# SIPM_readout.net
KiCad netlist of a schematic drawn in EAGLE
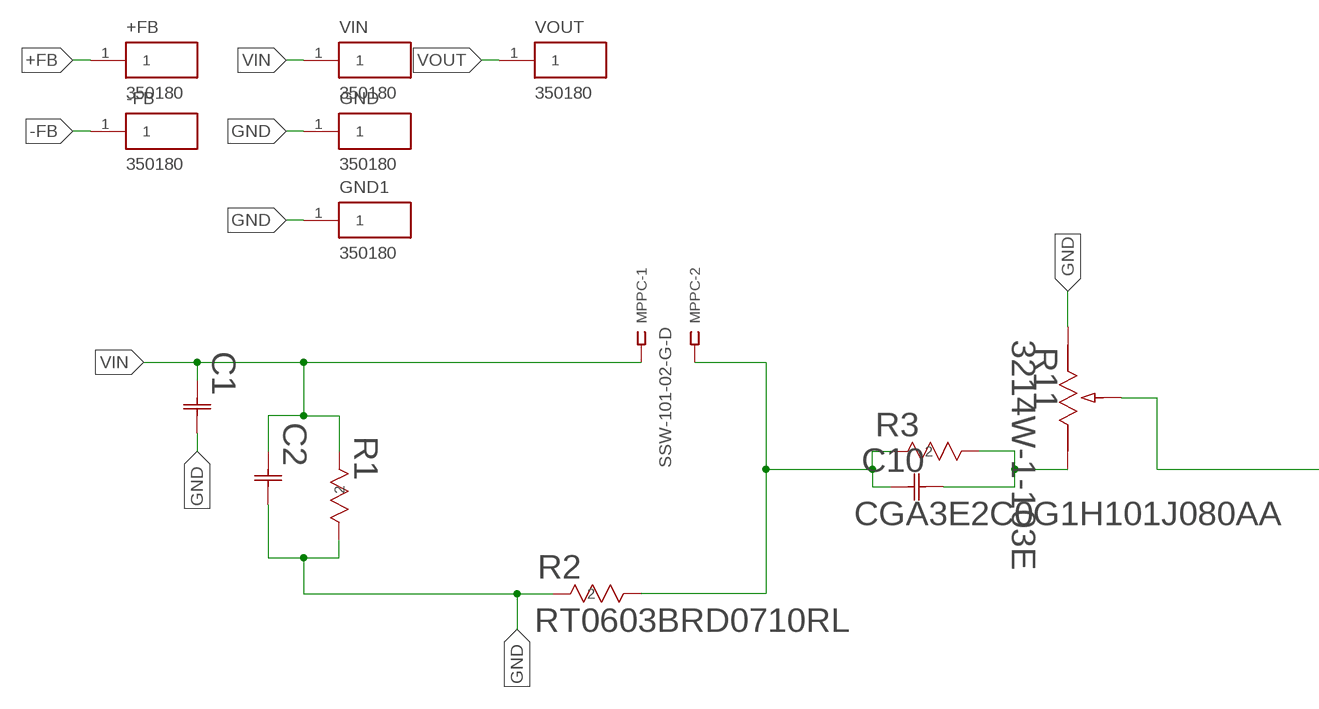
[diagram p0: schematic, sheet 1, part 1 of 2]
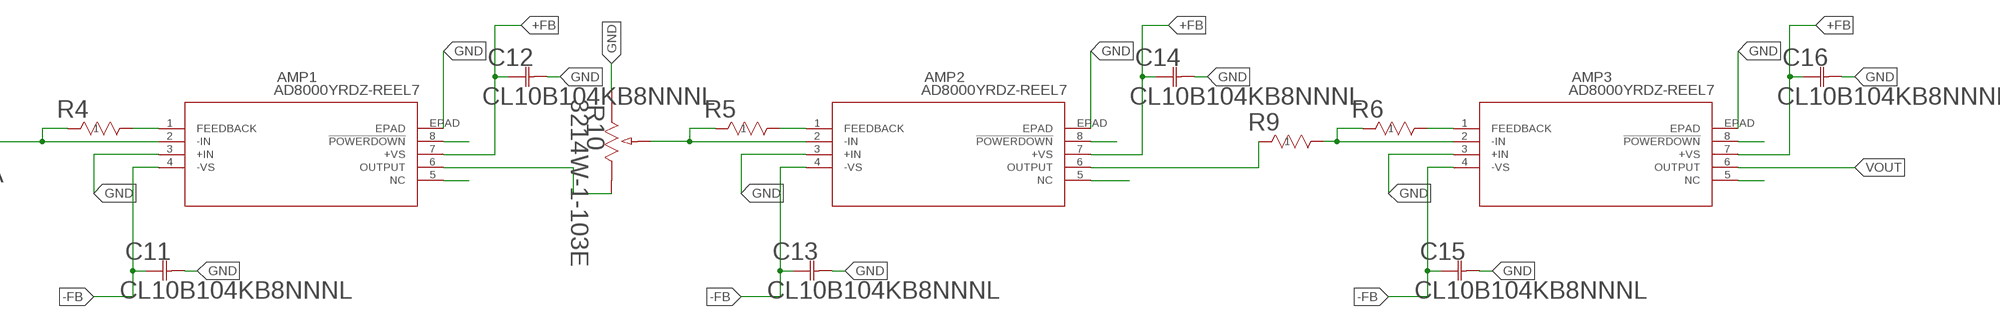
[diagram p1: schematic, sheet 1, part 2 of 2]

(export (version "E")
  (design (tool "Eeschema 10.0.6"))
  (components
    (comp (ref "+FB")
      (value "350180")
      (footprint "eagle-import:TE_350180")
      (fields (field (name "MF") "TE Connectivity"))
      (libsource (lib "eagle-import") (part "350180"))
    )
    (comp (ref "-FB")
      (value "350180")
      (footprint "eagle-import:TE_350180")
      (fields (field (name "MF") "TE Connectivity"))
      (libsource (lib "eagle-import") (part "350180"))
    )
    (comp (ref "AMP1")
      (value "AD8000YRDZ-REEL7")
      (footprint "eagle-import:RD_8_1_ADI")
      (fields (field (name "COPYRIGHT") "Copyright (C) 2018 Accelerated Designs. All rights reserved"))
      (libsource (lib "eagle-import") (part "AD8000YRDZ-REEL7"))
    )
    (comp (ref "AMP2")
      (value "AD8000YRDZ-REEL7")
      (footprint "eagle-import:RD_8_1_ADI")
      (fields (field (name "COPYRIGHT") "Copyright (C) 2018 Accelerated Designs. All rights reserved"))
      (libsource (lib "eagle-import") (part "AD8000YRDZ-REEL7"))
    )
    (comp (ref "AMP3")
      (value "AD8000YRDZ-REEL7")
      (footprint "eagle-import:RD_8_1_ADI")
      (fields (field (name "COPYRIGHT") "Copyright (C) 2018 Accelerated Designs. All rights reserved"))
      (libsource (lib "eagle-import") (part "AD8000YRDZ-REEL7"))
    )
    (comp (ref "C1")
      (value "CGA6P3X7R1H335K250AB")
      (footprint "eagle-import:CAP_3225_TDK")
      (libsource (lib "eagle-import") (part "CGA6P3X7R1H335K250AB"))
    )
    (comp (ref "C2")
      (value "C3225X7R1H105K160AA")
      (footprint "eagle-import:CAP_3225_TDK")
      (libsource (lib "eagle-import") (part "C3225X7R1H105K160AA"))
    )
    (comp (ref "C10")
      (value "CGA3E2C0G1H101J080AA")
      (footprint "eagle-import:CAP_1608_TDK")
      (libsource (lib "eagle-import") (part "CGA3E2C0G1H101J080AA"))
    )
    (comp (ref "C11")
      (value "CL10B104KB8NNNL")
      (footprint "eagle-import:CAP_CL10_SAM")
      (fields (field (name "COPYRIGHT") "Copyright (C) 2018 Accelerated Designs. All rights reserved"))
      (libsource (lib "eagle-import") (part "CL10B104KB8NNNL"))
    )
    (comp (ref "C12")
      (value "CL10B104KB8NNNL")
      (footprint "eagle-import:CAP_CL10_SAM")
      (fields (field (name "COPYRIGHT") "Copyright (C) 2018 Accelerated Designs. All rights reserved"))
      (libsource (lib "eagle-import") (part "CL10B104KB8NNNL"))
    )
    (comp (ref "C13")
      (value "CL10B104KB8NNNL")
      (footprint "eagle-import:CAP_CL10_SAM")
      (fields (field (name "COPYRIGHT") "Copyright (C) 2018 Accelerated Designs. All rights reserved"))
      (libsource (lib "eagle-import") (part "CL10B104KB8NNNL"))
    )
    (comp (ref "C14")
      (value "CL10B104KB8NNNL")
      (footprint "eagle-import:CAP_CL10_SAM")
      (fields (field (name "COPYRIGHT") "Copyright (C) 2018 Accelerated Designs. All rights reserved"))
      (libsource (lib "eagle-import") (part "CL10B104KB8NNNL"))
    )
    (comp (ref "C15")
      (value "CL10B104KB8NNNL")
      (footprint "eagle-import:CAP_CL10_SAM")
      (fields (field (name "COPYRIGHT") "Copyright (C) 2018 Accelerated Designs. All rights reserved"))
      (libsource (lib "eagle-import") (part "CL10B104KB8NNNL"))
    )
    (comp (ref "C16")
      (value "CL10B104KB8NNNL")
      (footprint "eagle-import:CAP_CL10_SAM")
      (fields (field (name "COPYRIGHT") "Copyright (C) 2018 Accelerated Designs. All rights reserved"))
      (libsource (lib "eagle-import") (part "CL10B104KB8NNNL"))
    )
    (comp (ref "GND")
      (value "350180")
      (footprint "eagle-import:TE_350180")
      (fields (field (name "MF") "TE Connectivity"))
      (libsource (lib "eagle-import") (part "350180"))
    )
    (comp (ref "GND1")
      (value "350180")
      (footprint "eagle-import:TE_350180")
      (fields (field (name "MF") "TE Connectivity"))
      (libsource (lib "eagle-import") (part "350180"))
    )
    (comp (ref "MPPC")
      (value "SSW-101-02-G-D")
      (footprint "eagle-import:SSW-101-02-G-D")
      (fields (field (name "MF") "Samtec Inc."))
      (libsource (lib "eagle-import") (part "SSW-101-02-G-D"))
    )
    (comp (ref "R1")
      (value "RC0603FR-072ML")
      (footprint "eagle-import:RC0603N_YAG")
      (libsource (lib "eagle-import") (part "RC0603FR-072ML"))
    )
    (comp (ref "R2")
      (value "RT0603BRD0710RL")
      (footprint "eagle-import:RC0603N_YAG")
      (libsource (lib "eagle-import") (part "RT0603BRD0710RL"))
    )
    (comp (ref "R3")
      (value "RT0603BRD0710RL")
      (footprint "eagle-import:RC0603N_YAG")
      (libsource (lib "eagle-import") (part "RT0603BRD0710RL"))
    )
    (comp (ref "R4")
      (value "ESR03EZPF1001")
      (footprint "eagle-import:RES_R0603_ROM")
      (libsource (lib "eagle-import") (part "ESR03EZPF1001"))
    )
    (comp (ref "R5")
      (value "ESR03EZPF1001")
      (footprint "eagle-import:RES_R0603_ROM")
      (libsource (lib "eagle-import") (part "ESR03EZPF1001"))
    )
    (comp (ref "R6")
      (value "ESR03EZPF1001")
      (footprint "eagle-import:RES_R0603_ROM")
      (libsource (lib "eagle-import") (part "ESR03EZPF1001"))
    )
    (comp (ref "R9")
      (value "ESR03EZPF1001")
      (footprint "eagle-import:RES_R0603_ROM")
      (libsource (lib "eagle-import") (part "ESR03EZPF1001"))
    )
    (comp (ref "R10")
      (value "3214W-1-103E")
      (footprint "eagle-import:POT_3214W")
      (libsource (lib "eagle-import") (part "3214W-1-103E"))
    )
    (comp (ref "R11")
      (value "3214W-1-103E")
      (footprint "eagle-import:POT_3214W")
      (libsource (lib "eagle-import") (part "3214W-1-103E"))
    )
    (comp (ref "VIN")
      (value "350180")
      (footprint "eagle-import:TE_350180")
      (fields (field (name "MF") "TE Connectivity"))
      (libsource (lib "eagle-import") (part "350180"))
    )
    (comp (ref "VOUT")
      (value "350180")
      (footprint "eagle-import:TE_350180")
      (fields (field (name "MF") "TE Connectivity"))
      (libsource (lib "eagle-import") (part "350180"))
    )
  )
  (nets
    (net (code "1") (name "+FB") (class "Default")
      (node (ref "+FB") (pin "1") (pinfunction "1_1") (pintype "passive"))
      (node (ref "AMP1") (pin "7") (pinfunction "+VS_7") (pintype "power_in"))
      (node (ref "AMP2") (pin "7") (pinfunction "+VS_7") (pintype "power_in"))
      (node (ref "AMP3") (pin "7") (pinfunction "+VS_7") (pintype "power_in"))
      (node (ref "C12") (pin "1") (pinfunction "1_1") (pintype "passive"))
      (node (ref "C14") (pin "1") (pinfunction "1_1") (pintype "passive"))
      (node (ref "C16") (pin "1") (pinfunction "1_1") (pintype "passive"))
    )
    (net (code "2") (name "-FB") (class "Default")
      (node (ref "-FB") (pin "1") (pinfunction "1_1") (pintype "passive"))
      (node (ref "AMP1") (pin "4") (pinfunction "-VS_4") (pintype "power_in"))
      (node (ref "AMP2") (pin "4") (pinfunction "-VS_4") (pintype "power_in"))
      (node (ref "AMP3") (pin "4") (pinfunction "-VS_4") (pintype "power_in"))
      (node (ref "C11") (pin "1") (pinfunction "1_1") (pintype "passive"))
      (node (ref "C13") (pin "1") (pinfunction "1_1") (pintype "passive"))
      (node (ref "C15") (pin "1") (pinfunction "1_1") (pintype "passive"))
    )
    (net (code "3") (name "GND") (class "Default")
      (node (ref "AMP1") (pin "3") (pinfunction "+IN_3") (pintype "input"))
      (node (ref "AMP1") (pin "EPAD") (pinfunction "EPAD_EPAD") (pintype "passive"))
      (node (ref "AMP2") (pin "3") (pinfunction "+IN_3") (pintype "input"))
      (node (ref "AMP2") (pin "EPAD") (pinfunction "EPAD_EPAD") (pintype "passive"))
      (node (ref "AMP3") (pin "3") (pinfunction "+IN_3") (pintype "input"))
      (node (ref "AMP3") (pin "EPAD") (pinfunction "EPAD_EPAD") (pintype "passive"))
      (node (ref "C1") (pin "2") (pinfunction "2_2") (pintype "passive"))
      (node (ref "C11") (pin "2") (pinfunction "2_2") (pintype "passive"))
      (node (ref "C12") (pin "2") (pinfunction "2_2") (pintype "passive"))
      (node (ref "C13") (pin "2") (pinfunction "2_2") (pintype "passive"))
      (node (ref "C14") (pin "2") (pinfunction "2_2") (pintype "passive"))
      (node (ref "C15") (pin "2") (pinfunction "2_2") (pintype "passive"))
      (node (ref "C16") (pin "2") (pinfunction "2_2") (pintype "passive"))
      (node (ref "C2") (pin "2") (pinfunction "2_2") (pintype "passive"))
      (node (ref "GND") (pin "1") (pinfunction "1_1") (pintype "passive"))
      (node (ref "GND1") (pin "1") (pinfunction "1_1") (pintype "passive"))
      (node (ref "R1") (pin "1") (pinfunction "1_1") (pintype "passive"))
      (node (ref "R10") (pin "1") (pinfunction "1_1") (pintype "passive"))
      (node (ref "R11") (pin "1") (pinfunction "1_1") (pintype "passive"))
      (node (ref "R2") (pin "2") (pinfunction "2_2") (pintype "passive"))
    )
    (net (code "4") (name "Net-(AMP1--IN)") (class "Default")
      (node (ref "AMP1") (pin "2") (pinfunction "-IN_2") (pintype "input"))
      (node (ref "R11") (pin "2") (pinfunction "2_2") (pintype "passive"))
      (node (ref "R4") (pin "1") (pinfunction "1_1") (pintype "passive"))
    )
    (net (code "5") (name "Net-(AMP1-FEEDBACK)") (class "Default")
      (node (ref "AMP1") (pin "1") (pinfunction "FEEDBACK_1") (pintype "passive"))
      (node (ref "R4") (pin "2") (pinfunction "2_2") (pintype "passive"))
    )
    (net (code "6") (name "Net-(AMP1-OUTPUT)") (class "Default")
      (node (ref "AMP1") (pin "6") (pinfunction "OUTPUT_6") (pintype "output"))
      (node (ref "R10") (pin "3") (pinfunction "3_3") (pintype "passive"))
    )
    (net (code "7") (name "Net-(AMP2--IN)") (class "Default")
      (node (ref "AMP2") (pin "2") (pinfunction "-IN_2") (pintype "input"))
      (node (ref "R10") (pin "2") (pinfunction "2_2") (pintype "passive"))
      (node (ref "R5") (pin "1") (pinfunction "1_1") (pintype "passive"))
    )
    (net (code "8") (name "Net-(AMP2-FEEDBACK)") (class "Default")
      (node (ref "AMP2") (pin "1") (pinfunction "FEEDBACK_1") (pintype "passive"))
      (node (ref "R5") (pin "2") (pinfunction "2_2") (pintype "passive"))
    )
    (net (code "9") (name "Net-(AMP2-OUTPUT)") (class "Default")
      (node (ref "AMP2") (pin "6") (pinfunction "OUTPUT_6") (pintype "output"))
      (node (ref "R9") (pin "1") (pinfunction "1_1") (pintype "passive"))
    )
    (net (code "10") (name "Net-(AMP3--IN)") (class "Default")
      (node (ref "AMP3") (pin "2") (pinfunction "-IN_2") (pintype "input"))
      (node (ref "R6") (pin "1") (pinfunction "1_1") (pintype "passive"))
      (node (ref "R9") (pin "2") (pinfunction "2_2") (pintype "passive"))
    )
    (net (code "11") (name "Net-(AMP3-FEEDBACK)") (class "Default")
      (node (ref "AMP3") (pin "1") (pinfunction "FEEDBACK_1") (pintype "passive"))
      (node (ref "R6") (pin "2") (pinfunction "2_2") (pintype "passive"))
    )
    (net (code "12") (name "Net-(C10-Pad2)") (class "Default")
      (node (ref "C10") (pin "2") (pinfunction "2_2") (pintype "passive"))
      (node (ref "R11") (pin "3") (pinfunction "3_3") (pintype "passive"))
      (node (ref "R3") (pin "1") (pinfunction "1_1") (pintype "passive"))
    )
    (net (code "13") (name "Net-(MPPCB-1)") (class "Default")
      (node (ref "C10") (pin "1") (pinfunction "1_1") (pintype "passive"))
      (node (ref "MPPC") (pin "2") (pinfunction "1_2") (pintype "passive"))
      (node (ref "R2") (pin "1") (pinfunction "1_1") (pintype "passive"))
      (node (ref "R3") (pin "2") (pinfunction "2_2") (pintype "passive"))
    )
    (net (code "14") (name "VIN") (class "Default")
      (node (ref "C1") (pin "1") (pinfunction "1_1") (pintype "passive"))
      (node (ref "C2") (pin "1") (pinfunction "1_1") (pintype "passive"))
      (node (ref "MPPC") (pin "1") (pinfunction "1_1") (pintype "passive"))
      (node (ref "R1") (pin "2") (pinfunction "2_2") (pintype "passive"))
      (node (ref "VIN") (pin "1") (pinfunction "1_1") (pintype "passive"))
    )
    (net (code "15") (name "VOUT") (class "Default")
      (node (ref "AMP3") (pin "6") (pinfunction "OUTPUT_6") (pintype "output"))
      (node (ref "VOUT") (pin "1") (pinfunction "1_1") (pintype "passive"))
    )
    (net (code "16") (name "unconnected-(AMP1-NC-Pad5)") (class "Default")
      (node (ref "AMP1") (pin "5") (pinfunction "NC_5") (pintype "no_connect"))
    )
    (net (code "17") (name "unconnected-(AMP1-~{POWERDOWN}-Pad8)") (class "Default")
      (node (ref "AMP1") (pin "8") (pinfunction "~{POWERDOWN}_8") (pintype "passive"))
    )
    (net (code "18") (name "unconnected-(AMP2-NC-Pad5)") (class "Default")
      (node (ref "AMP2") (pin "5") (pinfunction "NC_5") (pintype "no_connect"))
    )
    (net (code "19") (name "unconnected-(AMP2-~{POWERDOWN}-Pad8)") (class "Default")
      (node (ref "AMP2") (pin "8") (pinfunction "~{POWERDOWN}_8") (pintype "passive"))
    )
    (net (code "20") (name "unconnected-(AMP3-NC-Pad5)") (class "Default")
      (node (ref "AMP3") (pin "5") (pinfunction "NC_5") (pintype "no_connect"))
    )
    (net (code "21") (name "unconnected-(AMP3-~{POWERDOWN}-Pad8)") (class "Default")
      (node (ref "AMP3") (pin "8") (pinfunction "~{POWERDOWN}_8") (pintype "passive"))
    )
  )
)
